# FGG-6.net
KiCad netlist of a schematic drawn in EAGLE
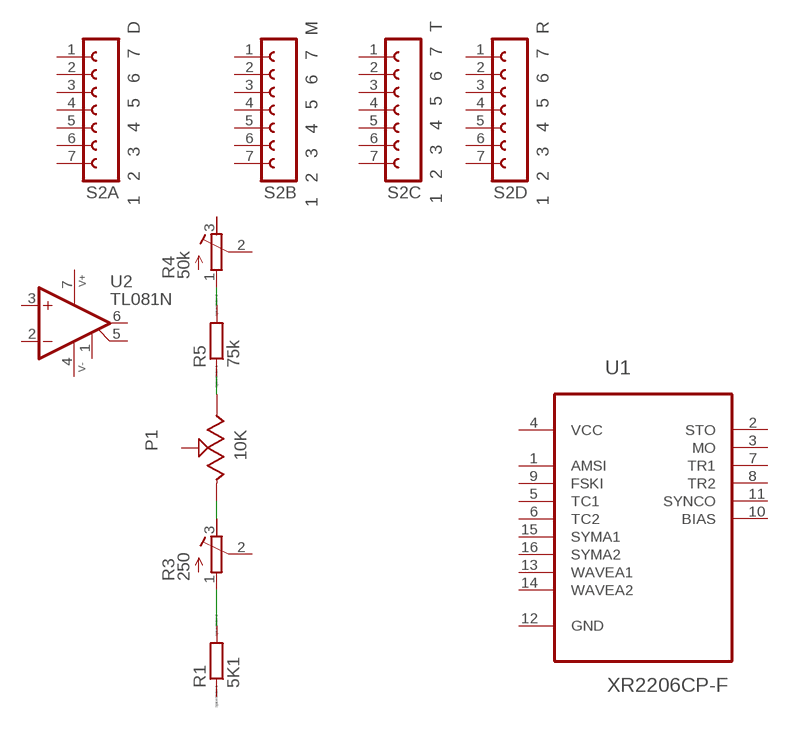
[diagram p0: schematic, sheet 1]

(export (version "E")
  (design (tool "Eeschema 10.0.6"))
  (components
    (comp (ref "P1")
      (value "10K")
      (footprint "eagle-import:91A1A-B28-B15L-ND")
      (fields
        (field (name "DIGIKEY_PARTNO") "91A1A-B28-B15L-ND")
        (field (name "MANUFACTURER") "Bourns Inc.")
        (field (name "MPN") "91A1A-B28-B15L")
        (field (name "CREATED_BY") "PCBLayout.com")
      )
      (libsource (lib "eagle-import") (part "91A1A-B28-B15L"))
    )
    (comp (ref "R1")
      (value "5K1")
      (footprint "eagle-import:0207_10")
      (libsource (lib "eagle-import") (part "R0207/10"))
    )
    (comp (ref "R3")
      (value "250")
      (footprint "eagle-import:RTRIM64W")
      (libsource (lib "eagle-import") (part "R-TRIMM64W"))
    )
    (comp (ref "R4")
      (value "50k")
      (footprint "eagle-import:RTRIM64W")
      (libsource (lib "eagle-import") (part "R-TRIMM64W"))
    )
    (comp (ref "R5")
      (value "75k")
      (footprint "eagle-import:0207_10")
      (libsource (lib "eagle-import") (part "R0207/10"))
    )
    (comp (ref "S2A")
      (value "1 2 3 4 5 6 7 D")
      (footprint "eagle-import:FE07")
      (libsource (lib "eagle-import") (part "FE07-1"))
    )
    (comp (ref "S2B")
      (value "1 2 3 4 5 6 7 M")
      (footprint "eagle-import:FE07")
      (libsource (lib "eagle-import") (part "FE07-1"))
    )
    (comp (ref "S2C")
      (value "1 2 3 4 5 6 7 T")
      (footprint "eagle-import:FE07")
      (libsource (lib "eagle-import") (part "FE07-1"))
    )
    (comp (ref "S2D")
      (value "1 2 3 4 5 6 7 R")
      (footprint "eagle-import:FE07")
      (libsource (lib "eagle-import") (part "FE07-1"))
    )
    (comp (ref "U1")
      (value "XR2206CP-F")
      (footprint "eagle-import:DIP254P762X533-16")
      (fields (field (name "MF") "MaxLinear, Inc."))
      (libsource (lib "eagle-import") (part "XR2206CP-F"))
    )
    (comp (ref "U2")
      (value "TL081N")
      (footprint "eagle-import:DIL08")
      (libsource (lib "eagle-import") (part "TL081N"))
    )
  )
  (nets
    (net (code "1") (name "/V+") (class "Default")
      (node (ref "U2") (pin "7") (pinfunction "V+_7") (pintype "power_in"))
    )
    (net (code "2") (name "/V-") (class "Default")
      (node (ref "U2") (pin "4") (pinfunction "V-_4") (pintype "power_in"))
    )
    (net (code "3") (name "/VCC") (class "Default")
      (node (ref "U1") (pin "4") (pinfunction "VCC_4") (pintype "power_in"))
    )
    (net (code "4") (name "Net-(P1-Pad3)") (class "Default")
      (node (ref "P1") (pin "3") (pinfunction "3_3") (pintype "passive"))
      (node (ref "R5") (pin "1") (pinfunction "1_1") (pintype "passive"))
    )
    (net (code "5") (name "Net-(R3-A)") (class "Default")
      (node (ref "R1") (pin "2") (pinfunction "2_2") (pintype "passive"))
      (node (ref "R3") (pin "1") (pinfunction "A_1") (pintype "passive"))
    )
    (net (code "6") (name "Net-(R3-E)") (class "Default")
      (node (ref "P1") (pin "1") (pinfunction "1_1") (pintype "passive"))
      (node (ref "R3") (pin "3") (pinfunction "E_3") (pintype "passive"))
    )
    (net (code "7") (name "Net-(R4-A)") (class "Default")
      (node (ref "R4") (pin "1") (pinfunction "A_1") (pintype "passive"))
      (node (ref "R5") (pin "2") (pinfunction "2_2") (pintype "passive"))
    )
    (net (code "8") (name "unconnected-(P1-Pad2)") (class "Default")
      (node (ref "P1") (pin "2") (pinfunction "2_2") (pintype "passive"))
    )
    (net (code "9") (name "unconnected-(R1-Pad1)") (class "Default")
      (node (ref "R1") (pin "1") (pinfunction "1_1") (pintype "passive"))
    )
    (net (code "10") (name "unconnected-(R3-S-Pad2)") (class "Default")
      (node (ref "R3") (pin "2") (pinfunction "S_2") (pintype "passive"))
    )
    (net (code "11") (name "unconnected-(R4-E-Pad3)") (class "Default")
      (node (ref "R4") (pin "3") (pinfunction "E_3") (pintype "passive"))
    )
    (net (code "12") (name "unconnected-(R4-S-Pad2)") (class "Default")
      (node (ref "R4") (pin "2") (pinfunction "S_2") (pintype "passive"))
    )
    (net (code "13") (name "unconnected-(S2A-Pad1)") (class "Default")
      (node (ref "S2A") (pin "1") (pinfunction "1_1") (pintype "passive"))
    )
    (net (code "14") (name "unconnected-(S2A-Pad2)") (class "Default")
      (node (ref "S2A") (pin "2") (pinfunction "2_2") (pintype "passive"))
    )
    (net (code "15") (name "unconnected-(S2A-Pad3)") (class "Default")
      (node (ref "S2A") (pin "3") (pinfunction "3_3") (pintype "passive"))
    )
    (net (code "16") (name "unconnected-(S2A-Pad4)") (class "Default")
      (node (ref "S2A") (pin "4") (pinfunction "4_4") (pintype "passive"))
    )
    (net (code "17") (name "unconnected-(S2A-Pad5)") (class "Default")
      (node (ref "S2A") (pin "5") (pinfunction "5_5") (pintype "passive"))
    )
    (net (code "18") (name "unconnected-(S2A-Pad6)") (class "Default")
      (node (ref "S2A") (pin "6") (pinfunction "6_6") (pintype "passive"))
    )
    (net (code "19") (name "unconnected-(S2A-Pad7)") (class "Default")
      (node (ref "S2A") (pin "7") (pinfunction "7_7") (pintype "passive"))
    )
    (net (code "20") (name "unconnected-(S2B-Pad1)") (class "Default")
      (node (ref "S2B") (pin "1") (pinfunction "1_1") (pintype "passive"))
    )
    (net (code "21") (name "unconnected-(S2B-Pad2)") (class "Default")
      (node (ref "S2B") (pin "2") (pinfunction "2_2") (pintype "passive"))
    )
    (net (code "22") (name "unconnected-(S2B-Pad3)") (class "Default")
      (node (ref "S2B") (pin "3") (pinfunction "3_3") (pintype "passive"))
    )
    (net (code "23") (name "unconnected-(S2B-Pad4)") (class "Default")
      (node (ref "S2B") (pin "4") (pinfunction "4_4") (pintype "passive"))
    )
    (net (code "24") (name "unconnected-(S2B-Pad5)") (class "Default")
      (node (ref "S2B") (pin "5") (pinfunction "5_5") (pintype "passive"))
    )
    (net (code "25") (name "unconnected-(S2B-Pad6)") (class "Default")
      (node (ref "S2B") (pin "6") (pinfunction "6_6") (pintype "passive"))
    )
    (net (code "26") (name "unconnected-(S2B-Pad7)") (class "Default")
      (node (ref "S2B") (pin "7") (pinfunction "7_7") (pintype "passive"))
    )
    (net (code "27") (name "unconnected-(S2C-Pad1)") (class "Default")
      (node (ref "S2C") (pin "1") (pinfunction "1_1") (pintype "passive"))
    )
    (net (code "28") (name "unconnected-(S2C-Pad2)") (class "Default")
      (node (ref "S2C") (pin "2") (pinfunction "2_2") (pintype "passive"))
    )
    (net (code "29") (name "unconnected-(S2C-Pad3)") (class "Default")
      (node (ref "S2C") (pin "3") (pinfunction "3_3") (pintype "passive"))
    )
    (net (code "30") (name "unconnected-(S2C-Pad4)") (class "Default")
      (node (ref "S2C") (pin "4") (pinfunction "4_4") (pintype "passive"))
    )
    (net (code "31") (name "unconnected-(S2C-Pad5)") (class "Default")
      (node (ref "S2C") (pin "5") (pinfunction "5_5") (pintype "passive"))
    )
    (net (code "32") (name "unconnected-(S2C-Pad6)") (class "Default")
      (node (ref "S2C") (pin "6") (pinfunction "6_6") (pintype "passive"))
    )
    (net (code "33") (name "unconnected-(S2C-Pad7)") (class "Default")
      (node (ref "S2C") (pin "7") (pinfunction "7_7") (pintype "passive"))
    )
    (net (code "34") (name "unconnected-(S2D-Pad1)") (class "Default")
      (node (ref "S2D") (pin "1") (pinfunction "1_1") (pintype "passive"))
    )
    (net (code "35") (name "unconnected-(S2D-Pad2)") (class "Default")
      (node (ref "S2D") (pin "2") (pinfunction "2_2") (pintype "passive"))
    )
    (net (code "36") (name "unconnected-(S2D-Pad3)") (class "Default")
      (node (ref "S2D") (pin "3") (pinfunction "3_3") (pintype "passive"))
    )
    (net (code "37") (name "unconnected-(S2D-Pad4)") (class "Default")
      (node (ref "S2D") (pin "4") (pinfunction "4_4") (pintype "passive"))
    )
    (net (code "38") (name "unconnected-(S2D-Pad5)") (class "Default")
      (node (ref "S2D") (pin "5") (pinfunction "5_5") (pintype "passive"))
    )
    (net (code "39") (name "unconnected-(S2D-Pad6)") (class "Default")
      (node (ref "S2D") (pin "6") (pinfunction "6_6") (pintype "passive"))
    )
    (net (code "40") (name "unconnected-(S2D-Pad7)") (class "Default")
      (node (ref "S2D") (pin "7") (pinfunction "7_7") (pintype "passive"))
    )
    (net (code "41") (name "unconnected-(U1-AMSI-Pad1)") (class "Default")
      (node (ref "U1") (pin "1") (pinfunction "AMSI_1") (pintype "input"))
    )
    (net (code "42") (name "unconnected-(U1-BIAS-Pad10)") (class "Default")
      (node (ref "U1") (pin "10") (pinfunction "BIAS_10") (pintype "output"))
    )
    (net (code "43") (name "unconnected-(U1-FSKI-Pad9)") (class "Default")
      (node (ref "U1") (pin "9") (pinfunction "FSKI_9") (pintype "input"))
    )
    (net (code "44") (name "unconnected-(U1-GND-Pad12)") (class "Default")
      (node (ref "U1") (pin "12") (pinfunction "GND_12") (pintype "passive"))
    )
    (net (code "45") (name "unconnected-(U1-MO-Pad3)") (class "Default")
      (node (ref "U1") (pin "3") (pinfunction "MO_3") (pintype "output"))
    )
    (net (code "46") (name "unconnected-(U1-STO-Pad2)") (class "Default")
      (node (ref "U1") (pin "2") (pinfunction "STO_2") (pintype "output"))
    )
    (net (code "47") (name "unconnected-(U1-SYMA1-Pad15)") (class "Default")
      (node (ref "U1") (pin "15") (pinfunction "SYMA1_15") (pintype "input"))
    )
    (net (code "48") (name "unconnected-(U1-SYMA2-Pad16)") (class "Default")
      (node (ref "U1") (pin "16") (pinfunction "SYMA2_16") (pintype "input"))
    )
    (net (code "49") (name "unconnected-(U1-SYNCO-Pad11)") (class "Default")
      (node (ref "U1") (pin "11") (pinfunction "SYNCO_11") (pintype "output"))
    )
    (net (code "50") (name "unconnected-(U1-TC1-Pad5)") (class "Default")
      (node (ref "U1") (pin "5") (pinfunction "TC1_5") (pintype "input"))
    )
    (net (code "51") (name "unconnected-(U1-TC2-Pad6)") (class "Default")
      (node (ref "U1") (pin "6") (pinfunction "TC2_6") (pintype "input"))
    )
    (net (code "52") (name "unconnected-(U1-TR1-Pad7)") (class "Default")
      (node (ref "U1") (pin "7") (pinfunction "TR1_7") (pintype "output"))
    )
    (net (code "53") (name "unconnected-(U1-TR2-Pad8)") (class "Default")
      (node (ref "U1") (pin "8") (pinfunction "TR2_8") (pintype "output"))
    )
    (net (code "54") (name "unconnected-(U1-WAVEA1-Pad13)") (class "Default")
      (node (ref "U1") (pin "13") (pinfunction "WAVEA1_13") (pintype "input"))
    )
    (net (code "55") (name "unconnected-(U1-WAVEA2-Pad14)") (class "Default")
      (node (ref "U1") (pin "14") (pinfunction "WAVEA2_14") (pintype "input"))
    )
    (net (code "56") (name "unconnected-(U2A-NULL1-Pad1)") (class "Default")
      (node (ref "U2") (pin "1") (pinfunction "NULL1_1") (pintype "passive"))
    )
    (net (code "57") (name "unconnected-(U2A-NULL2-Pad5)") (class "Default")
      (node (ref "U2") (pin "5") (pinfunction "NULL2_5") (pintype "passive"))
    )
    (net (code "58") (name "unconnected-(U2B-+IN-Pad3)") (class "Default")
      (node (ref "U2") (pin "3") (pinfunction "+IN_3") (pintype "input"))
    )
    (net (code "59") (name "unconnected-(U2B--IN-Pad2)") (class "Default")
      (node (ref "U2") (pin "2") (pinfunction "-IN_2") (pintype "input"))
    )
    (net (code "60") (name "unconnected-(U2B-OUT-Pad6)") (class "Default")
      (node (ref "U2") (pin "6") (pinfunction "OUT_6") (pintype "output"))
    )
  )
)
